# Power.net
KiCad netlist of a schematic drawn in Altium Designer
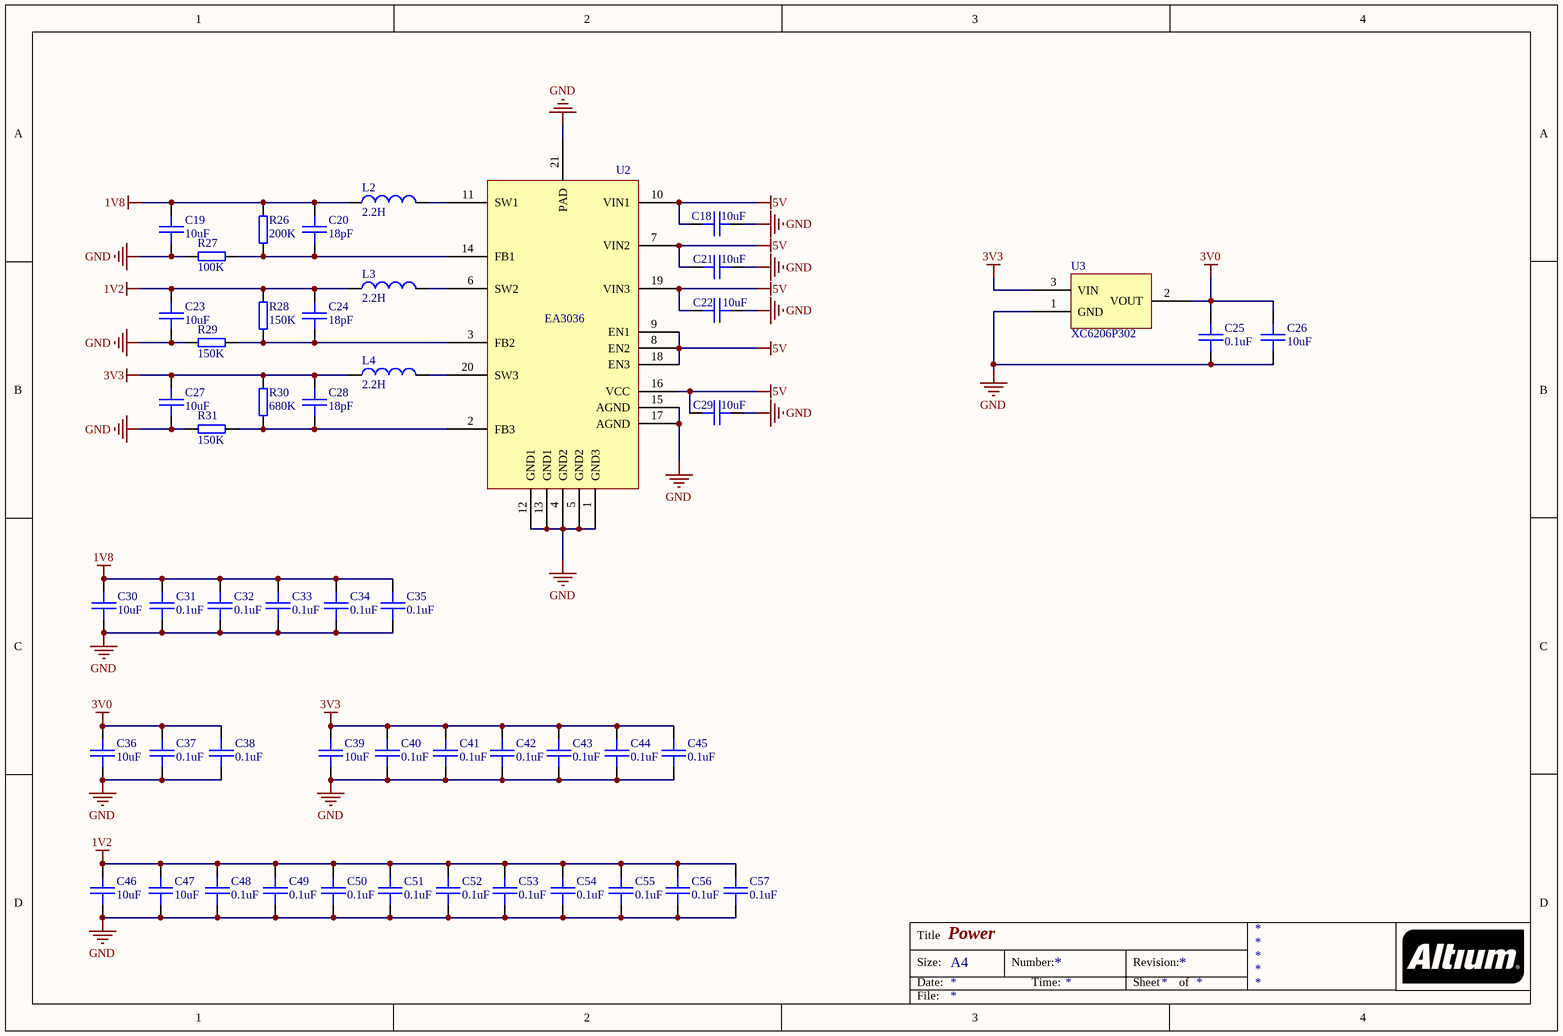
[diagram p0: Power.SchDoc]

(export (version "E")
  (design (tool "Eeschema 10.0.6"))
  (components
    (comp (ref "C18")
      (value "10uF")
      (footprint "CAP-1206")
      (description "陶瓷贴片电容1206")
      (fields (field (name "TOLERANCE") "10%") (field (name "VOLTAGE") "50V"))
      (libsource (lib "momo") (part "C_1206"))
    )
    (comp (ref "C19")
      (value "10uF")
      (footprint "CAP-1206")
      (description "陶瓷贴片电容1206")
      (fields (field (name "TOLERANCE") "10%") (field (name "VOLTAGE") "50V"))
      (libsource (lib "momo") (part "C_1206"))
    )
    (comp (ref "C20")
      (value "18pF")
      (footprint "CAP-0603")
      (description "陶瓷贴片电容0603")
      (fields (field (name "TOLERANCE") "10%") (field (name "VOLTAGE") "50V"))
      (libsource (lib "momo") (part "C_0603"))
    )
    (comp (ref "C21")
      (value "10uF")
      (footprint "CAP-1206")
      (description "陶瓷贴片电容1206")
      (fields (field (name "TOLERANCE") "10%") (field (name "VOLTAGE") "50V"))
      (libsource (lib "momo") (part "C_1206"))
    )
    (comp (ref "C22")
      (value "10uF")
      (footprint "CAP-1206")
      (description "陶瓷贴片电容1206")
      (fields (field (name "TOLERANCE") "10%") (field (name "VOLTAGE") "50V"))
      (libsource (lib "momo") (part "C_1206"))
    )
    (comp (ref "C23")
      (value "10uF")
      (footprint "CAP-1206")
      (description "陶瓷贴片电容1206")
      (fields (field (name "TOLERANCE") "10%") (field (name "VOLTAGE") "50V"))
      (libsource (lib "momo") (part "C_1206"))
    )
    (comp (ref "C24")
      (value "18pF")
      (footprint "CAP-0603")
      (description "陶瓷贴片电容0603")
      (fields (field (name "TOLERANCE") "10%") (field (name "VOLTAGE") "50V"))
      (libsource (lib "momo") (part "C_0603"))
    )
    (comp (ref "C25")
      (value "0.1uF")
      (footprint "CAP-0603")
      (description "陶瓷贴片电容0603")
      (fields (field (name "TOLERANCE") "10%") (field (name "VOLTAGE") "50V"))
      (libsource (lib "momo") (part "C_0603"))
    )
    (comp (ref "C26")
      (value "10uF")
      (footprint "CAP-1206")
      (description "陶瓷贴片电容1206")
      (fields (field (name "TOLERANCE") "10%") (field (name "VOLTAGE") "50V"))
      (libsource (lib "momo") (part "C_1206"))
    )
    (comp (ref "C27")
      (value "10uF")
      (footprint "CAP-1206")
      (description "陶瓷贴片电容1206")
      (fields (field (name "TOLERANCE") "10%") (field (name "VOLTAGE") "50V"))
      (libsource (lib "momo") (part "C_1206"))
    )
    (comp (ref "C28")
      (value "18pF")
      (footprint "CAP-0603")
      (description "陶瓷贴片电容0603")
      (fields (field (name "TOLERANCE") "10%") (field (name "VOLTAGE") "50V"))
      (libsource (lib "momo") (part "C_0603"))
    )
    (comp (ref "C29")
      (value "10uF")
      (footprint "CAP-1206")
      (description "陶瓷贴片电容1206")
      (fields (field (name "TOLERANCE") "10%") (field (name "VOLTAGE") "50V"))
      (libsource (lib "momo") (part "C_1206"))
    )
    (comp (ref "C30")
      (value "10uF")
      (footprint "CAP-0603")
      (description "陶瓷贴片电容0603")
      (fields (field (name "TOLERANCE") "10%") (field (name "VOLTAGE") "50V"))
      (libsource (lib "momo") (part "C_0603"))
    )
    (comp (ref "C31")
      (value "0.1uF")
      (footprint "CAP-0603")
      (description "陶瓷贴片电容0603")
      (fields (field (name "TOLERANCE") "10%") (field (name "VOLTAGE") "50V"))
      (libsource (lib "momo") (part "C_0603"))
    )
    (comp (ref "C32")
      (value "0.1uF")
      (footprint "CAP-0603")
      (description "陶瓷贴片电容0603")
      (fields (field (name "TOLERANCE") "10%") (field (name "VOLTAGE") "50V"))
      (libsource (lib "momo") (part "C_0603"))
    )
    (comp (ref "C33")
      (value "0.1uF")
      (footprint "CAP-0603")
      (description "陶瓷贴片电容0603")
      (fields (field (name "TOLERANCE") "10%") (field (name "VOLTAGE") "50V"))
      (libsource (lib "momo") (part "C_0603"))
    )
    (comp (ref "C34")
      (value "0.1uF")
      (footprint "CAP-0603")
      (description "陶瓷贴片电容0603")
      (fields (field (name "TOLERANCE") "10%") (field (name "VOLTAGE") "50V"))
      (libsource (lib "momo") (part "C_0603"))
    )
    (comp (ref "C35")
      (value "0.1uF")
      (footprint "CAP-0603")
      (description "陶瓷贴片电容0603")
      (fields (field (name "TOLERANCE") "10%") (field (name "VOLTAGE") "50V"))
      (libsource (lib "momo") (part "C_0603"))
    )
    (comp (ref "C36")
      (value "10uF")
      (footprint "CAP-0603")
      (description "陶瓷贴片电容0603")
      (fields (field (name "TOLERANCE") "10%") (field (name "VOLTAGE") "50V"))
      (libsource (lib "momo") (part "C_0603"))
    )
    (comp (ref "C37")
      (value "0.1uF")
      (footprint "CAP-0603")
      (description "陶瓷贴片电容0603")
      (fields (field (name "TOLERANCE") "10%") (field (name "VOLTAGE") "50V"))
      (libsource (lib "momo") (part "C_0603"))
    )
    (comp (ref "C38")
      (value "0.1uF")
      (footprint "CAP-0603")
      (description "陶瓷贴片电容0603")
      (fields (field (name "TOLERANCE") "10%") (field (name "VOLTAGE") "50V"))
      (libsource (lib "momo") (part "C_0603"))
    )
    (comp (ref "C39")
      (value "10uF")
      (footprint "CAP-0603")
      (description "陶瓷贴片电容0603")
      (fields (field (name "TOLERANCE") "10%") (field (name "VOLTAGE") "50V"))
      (libsource (lib "momo") (part "C_0603"))
    )
    (comp (ref "C40")
      (value "0.1uF")
      (footprint "CAP-0603")
      (description "陶瓷贴片电容0603")
      (fields (field (name "TOLERANCE") "10%") (field (name "VOLTAGE") "50V"))
      (libsource (lib "momo") (part "C_0603"))
    )
    (comp (ref "C41")
      (value "0.1uF")
      (footprint "CAP-0603")
      (description "陶瓷贴片电容0603")
      (fields (field (name "TOLERANCE") "10%") (field (name "VOLTAGE") "50V"))
      (libsource (lib "momo") (part "C_0603"))
    )
    (comp (ref "C42")
      (value "0.1uF")
      (footprint "CAP-0603")
      (description "陶瓷贴片电容0603")
      (fields (field (name "TOLERANCE") "10%") (field (name "VOLTAGE") "50V"))
      (libsource (lib "momo") (part "C_0603"))
    )
    (comp (ref "C43")
      (value "0.1uF")
      (footprint "CAP-0603")
      (description "陶瓷贴片电容0603")
      (fields (field (name "TOLERANCE") "10%") (field (name "VOLTAGE") "50V"))
      (libsource (lib "momo") (part "C_0603"))
    )
    (comp (ref "C44")
      (value "0.1uF")
      (footprint "CAP-0603")
      (description "陶瓷贴片电容0603")
      (fields (field (name "TOLERANCE") "10%") (field (name "VOLTAGE") "50V"))
      (libsource (lib "momo") (part "C_0603"))
    )
    (comp (ref "C45")
      (value "0.1uF")
      (footprint "CAP-0603")
      (description "陶瓷贴片电容0603")
      (fields (field (name "TOLERANCE") "10%") (field (name "VOLTAGE") "50V"))
      (libsource (lib "momo") (part "C_0603"))
    )
    (comp (ref "C46")
      (value "10uF")
      (footprint "CAP-0603")
      (description "陶瓷贴片电容0603")
      (fields (field (name "TOLERANCE") "10%") (field (name "VOLTAGE") "50V"))
      (libsource (lib "momo") (part "C_0603"))
    )
    (comp (ref "C47")
      (value "10uF")
      (footprint "CAP-0603")
      (description "陶瓷贴片电容0603")
      (fields (field (name "TOLERANCE") "10%") (field (name "VOLTAGE") "50V"))
      (libsource (lib "momo") (part "C_0603"))
    )
    (comp (ref "C48")
      (value "0.1uF")
      (footprint "CAP-0603")
      (description "陶瓷贴片电容0603")
      (fields (field (name "TOLERANCE") "10%") (field (name "VOLTAGE") "50V"))
      (libsource (lib "momo") (part "C_0603"))
    )
    (comp (ref "C49")
      (value "0.1uF")
      (footprint "CAP-0603")
      (description "陶瓷贴片电容0603")
      (fields (field (name "TOLERANCE") "10%") (field (name "VOLTAGE") "50V"))
      (libsource (lib "momo") (part "C_0603"))
    )
    (comp (ref "C50")
      (value "0.1uF")
      (footprint "CAP-0603")
      (description "陶瓷贴片电容0603")
      (fields (field (name "TOLERANCE") "10%") (field (name "VOLTAGE") "50V"))
      (libsource (lib "momo") (part "C_0603"))
    )
    (comp (ref "C51")
      (value "0.1uF")
      (footprint "CAP-0603")
      (description "陶瓷贴片电容0603")
      (fields (field (name "TOLERANCE") "10%") (field (name "VOLTAGE") "50V"))
      (libsource (lib "momo") (part "C_0603"))
    )
    (comp (ref "C52")
      (value "0.1uF")
      (footprint "CAP-0603")
      (description "陶瓷贴片电容0603")
      (fields (field (name "TOLERANCE") "10%") (field (name "VOLTAGE") "50V"))
      (libsource (lib "momo") (part "C_0603"))
    )
    (comp (ref "C53")
      (value "0.1uF")
      (footprint "CAP-0603")
      (description "陶瓷贴片电容0603")
      (fields (field (name "TOLERANCE") "10%") (field (name "VOLTAGE") "50V"))
      (libsource (lib "momo") (part "C_0603"))
    )
    (comp (ref "C54")
      (value "0.1uF")
      (footprint "CAP-0603")
      (description "陶瓷贴片电容0603")
      (fields (field (name "TOLERANCE") "10%") (field (name "VOLTAGE") "50V"))
      (libsource (lib "momo") (part "C_0603"))
    )
    (comp (ref "C55")
      (value "0.1uF")
      (footprint "CAP-0603")
      (description "陶瓷贴片电容0603")
      (fields (field (name "TOLERANCE") "10%") (field (name "VOLTAGE") "50V"))
      (libsource (lib "momo") (part "C_0603"))
    )
    (comp (ref "C56")
      (value "0.1uF")
      (footprint "CAP-0603")
      (description "陶瓷贴片电容0603")
      (fields (field (name "TOLERANCE") "10%") (field (name "VOLTAGE") "50V"))
      (libsource (lib "momo") (part "C_0603"))
    )
    (comp (ref "C57")
      (value "0.1uF")
      (footprint "CAP-0603")
      (description "陶瓷贴片电容0603")
      (fields (field (name "TOLERANCE") "10%") (field (name "VOLTAGE") "50V"))
      (libsource (lib "momo") (part "C_0603"))
    )
    (comp (ref "L2")
      (value "2.2H")
      (footprint "L-PWR-6028")
      (description "功率电感")
      (fields (field (name "TOLERANCE") "20%"))
      (libsource (lib "momo") (part "L_Power"))
    )
    (comp (ref "L3")
      (value "2.2H")
      (footprint "L-PWR-6028")
      (description "功率电感")
      (fields (field (name "TOLERANCE") "20%"))
      (libsource (lib "momo") (part "L_Power"))
    )
    (comp (ref "L4")
      (value "2.2H")
      (footprint "L-PWR-6028")
      (description "功率电感")
      (fields (field (name "TOLERANCE") "20%"))
      (libsource (lib "momo") (part "L_Power"))
    )
    (comp (ref "R26")
      (value "200K")
      (footprint "RES-0603")
      (description "贴片电阻0603")
      (fields (field (name "TOLERANCE") "5%") (field (name "VOLTAGE") "50V"))
      (libsource (lib "momo") (part "R_0603"))
    )
    (comp (ref "R27")
      (value "100K")
      (footprint "RES-0603")
      (description "贴片电阻0603")
      (fields (field (name "TOLERANCE") "5%") (field (name "VOLTAGE") "50V"))
      (libsource (lib "momo") (part "R_0603"))
    )
    (comp (ref "R28")
      (value "150K")
      (footprint "RES-0603")
      (description "贴片电阻0603")
      (fields (field (name "TOLERANCE") "5%") (field (name "VOLTAGE") "50V"))
      (libsource (lib "momo") (part "R_0603"))
    )
    (comp (ref "R29")
      (value "150K")
      (footprint "RES-0603")
      (description "贴片电阻0603")
      (fields (field (name "TOLERANCE") "5%") (field (name "VOLTAGE") "50V"))
      (libsource (lib "momo") (part "R_0603"))
    )
    (comp (ref "R30")
      (value "680K")
      (footprint "RES-0603")
      (description "贴片电阻0603")
      (fields (field (name "TOLERANCE") "5%") (field (name "VOLTAGE") "50V"))
      (libsource (lib "momo") (part "R_0603"))
    )
    (comp (ref "R31")
      (value "150K")
      (footprint "RES-0603")
      (description "贴片电阻0603")
      (fields (field (name "TOLERANCE") "5%") (field (name "VOLTAGE") "50V"))
      (libsource (lib "momo") (part "R_0603"))
    )
    (comp (ref "U2")
      (value "EA3036")
      (footprint "QFN20-3X3")
      (description "3CH Power Management IC")
      (libsource (lib "momo") (part "EA3036"))
    )
    (comp (ref "U3")
      (value "XC6206P302")
      (footprint "SOT-23-3L")
      (description "XC6206 LDO=3V")
      (libsource (lib "momo") (part "XC6206"))
    )
  )
  (nets
    (net (code "1") (name "1V2") (class "Default")
      (node (ref "C23") (pin "2") (pinfunction "2_2") (pintype "passive"))
      (node (ref "C24") (pin "1") (pinfunction "1_1") (pintype "passive"))
      (node (ref "C46") (pin "1") (pinfunction "1_1") (pintype "passive"))
      (node (ref "C47") (pin "1") (pinfunction "1_1") (pintype "passive"))
      (node (ref "C48") (pin "1") (pinfunction "1_1") (pintype "passive"))
      (node (ref "C49") (pin "1") (pinfunction "1_1") (pintype "passive"))
      (node (ref "C50") (pin "1") (pinfunction "1_1") (pintype "passive"))
      (node (ref "C51") (pin "1") (pinfunction "1_1") (pintype "passive"))
      (node (ref "C52") (pin "1") (pinfunction "1_1") (pintype "passive"))
      (node (ref "C53") (pin "1") (pinfunction "1_1") (pintype "passive"))
      (node (ref "C54") (pin "1") (pinfunction "1_1") (pintype "passive"))
      (node (ref "C55") (pin "1") (pinfunction "1_1") (pintype "passive"))
      (node (ref "C56") (pin "1") (pinfunction "1_1") (pintype "passive"))
      (node (ref "C57") (pin "1") (pinfunction "1_1") (pintype "passive"))
      (node (ref "L3") (pin "1") (pinfunction "1_1") (pintype "passive"))
      (node (ref "R28") (pin "2") (pinfunction "2_2") (pintype "passive"))
    )
    (net (code "2") (name "1V8") (class "Default")
      (node (ref "C19") (pin "2") (pinfunction "2_2") (pintype "passive"))
      (node (ref "C20") (pin "1") (pinfunction "1_1") (pintype "passive"))
      (node (ref "C30") (pin "1") (pinfunction "1_1") (pintype "passive"))
      (node (ref "C31") (pin "1") (pinfunction "1_1") (pintype "passive"))
      (node (ref "C32") (pin "1") (pinfunction "1_1") (pintype "passive"))
      (node (ref "C33") (pin "1") (pinfunction "1_1") (pintype "passive"))
      (node (ref "C34") (pin "1") (pinfunction "1_1") (pintype "passive"))
      (node (ref "C35") (pin "1") (pinfunction "1_1") (pintype "passive"))
      (node (ref "L2") (pin "1") (pinfunction "1_1") (pintype "passive"))
      (node (ref "R26") (pin "2") (pinfunction "2_2") (pintype "passive"))
    )
    (net (code "3") (name "3V0") (class "Default")
      (node (ref "C25") (pin "1") (pinfunction "1_1") (pintype "passive"))
      (node (ref "C26") (pin "1") (pinfunction "1_1") (pintype "passive"))
      (node (ref "C36") (pin "1") (pinfunction "1_1") (pintype "passive"))
      (node (ref "C37") (pin "1") (pinfunction "1_1") (pintype "passive"))
      (node (ref "C38") (pin "1") (pinfunction "1_1") (pintype "passive"))
      (node (ref "U3") (pin "2") (pinfunction "VOUT_2") (pintype "power_in"))
    )
    (net (code "4") (name "3V3") (class "Default")
      (node (ref "C27") (pin "2") (pinfunction "2_2") (pintype "passive"))
      (node (ref "C28") (pin "1") (pinfunction "1_1") (pintype "passive"))
      (node (ref "C39") (pin "1") (pinfunction "1_1") (pintype "passive"))
      (node (ref "C40") (pin "1") (pinfunction "1_1") (pintype "passive"))
      (node (ref "C41") (pin "1") (pinfunction "1_1") (pintype "passive"))
      (node (ref "C42") (pin "1") (pinfunction "1_1") (pintype "passive"))
      (node (ref "C43") (pin "1") (pinfunction "1_1") (pintype "passive"))
      (node (ref "C44") (pin "1") (pinfunction "1_1") (pintype "passive"))
      (node (ref "C45") (pin "1") (pinfunction "1_1") (pintype "passive"))
      (node (ref "L4") (pin "1") (pinfunction "1_1") (pintype "passive"))
      (node (ref "R30") (pin "2") (pinfunction "2_2") (pintype "passive"))
      (node (ref "U3") (pin "3") (pinfunction "VIN_3") (pintype "power_in"))
    )
    (net (code "5") (name "5V") (class "Default")
      (node (ref "C18") (pin "2") (pinfunction "2_2") (pintype "passive"))
      (node (ref "C21") (pin "2") (pinfunction "2_2") (pintype "passive"))
      (node (ref "C22") (pin "2") (pinfunction "2_2") (pintype "passive"))
      (node (ref "C29") (pin "2") (pinfunction "2_2") (pintype "passive"))
      (node (ref "U2") (pin "10") (pinfunction "VIN1_10") (pintype "power_in"))
      (node (ref "U2") (pin "16") (pinfunction "VCC_16") (pintype "power_in"))
      (node (ref "U2") (pin "18") (pinfunction "EN3_18") (pintype "power_in"))
      (node (ref "U2") (pin "19") (pinfunction "VIN3_19") (pintype "power_in"))
      (node (ref "U2") (pin "7") (pinfunction "VIN2_7") (pintype "power_in"))
      (node (ref "U2") (pin "8") (pinfunction "EN2_8") (pintype "power_in"))
      (node (ref "U2") (pin "9") (pinfunction "EN1_9") (pintype "power_in"))
    )
    (net (code "6") (name "GND") (class "Default")
      (node (ref "C18") (pin "1") (pinfunction "1_1") (pintype "passive"))
      (node (ref "C19") (pin "1") (pinfunction "1_1") (pintype "passive"))
      (node (ref "C21") (pin "1") (pinfunction "1_1") (pintype "passive"))
      (node (ref "C22") (pin "1") (pinfunction "1_1") (pintype "passive"))
      (node (ref "C23") (pin "1") (pinfunction "1_1") (pintype "passive"))
      (node (ref "C25") (pin "2") (pinfunction "2_2") (pintype "passive"))
      (node (ref "C26") (pin "2") (pinfunction "2_2") (pintype "passive"))
      (node (ref "C27") (pin "1") (pinfunction "1_1") (pintype "passive"))
      (node (ref "C29") (pin "1") (pinfunction "1_1") (pintype "passive"))
      (node (ref "C30") (pin "2") (pinfunction "2_2") (pintype "passive"))
      (node (ref "C31") (pin "2") (pinfunction "2_2") (pintype "passive"))
      (node (ref "C32") (pin "2") (pinfunction "2_2") (pintype "passive"))
      (node (ref "C33") (pin "2") (pinfunction "2_2") (pintype "passive"))
      (node (ref "C34") (pin "2") (pinfunction "2_2") (pintype "passive"))
      (node (ref "C35") (pin "2") (pinfunction "2_2") (pintype "passive"))
      (node (ref "C36") (pin "2") (pinfunction "2_2") (pintype "passive"))
      (node (ref "C37") (pin "2") (pinfunction "2_2") (pintype "passive"))
      (node (ref "C38") (pin "2") (pinfunction "2_2") (pintype "passive"))
      (node (ref "C39") (pin "2") (pinfunction "2_2") (pintype "passive"))
      (node (ref "C40") (pin "2") (pinfunction "2_2") (pintype "passive"))
      (node (ref "C41") (pin "2") (pinfunction "2_2") (pintype "passive"))
      (node (ref "C42") (pin "2") (pinfunction "2_2") (pintype "passive"))
      (node (ref "C43") (pin "2") (pinfunction "2_2") (pintype "passive"))
      (node (ref "C44") (pin "2") (pinfunction "2_2") (pintype "passive"))
      (node (ref "C45") (pin "2") (pinfunction "2_2") (pintype "passive"))
      (node (ref "C46") (pin "2") (pinfunction "2_2") (pintype "passive"))
      (node (ref "C47") (pin "2") (pinfunction "2_2") (pintype "passive"))
      (node (ref "C48") (pin "2") (pinfunction "2_2") (pintype "passive"))
      (node (ref "C49") (pin "2") (pinfunction "2_2") (pintype "passive"))
      (node (ref "C50") (pin "2") (pinfunction "2_2") (pintype "passive"))
      (node (ref "C51") (pin "2") (pinfunction "2_2") (pintype "passive"))
      (node (ref "C52") (pin "2") (pinfunction "2_2") (pintype "passive"))
      (node (ref "C53") (pin "2") (pinfunction "2_2") (pintype "passive"))
      (node (ref "C54") (pin "2") (pinfunction "2_2") (pintype "passive"))
      (node (ref "C55") (pin "2") (pinfunction "2_2") (pintype "passive"))
      (node (ref "C56") (pin "2") (pinfunction "2_2") (pintype "passive"))
      (node (ref "C57") (pin "2") (pinfunction "2_2") (pintype "passive"))
      (node (ref "R27") (pin "2") (pinfunction "2_2") (pintype "passive"))
      (node (ref "R29") (pin "2") (pinfunction "2_2") (pintype "passive"))
      (node (ref "R31") (pin "2") (pinfunction "2_2") (pintype "passive"))
      (node (ref "U2") (pin "1") (pinfunction "GND3_1") (pintype "power_in"))
      (node (ref "U2") (pin "12") (pinfunction "GND1_12") (pintype "power_in"))
      (node (ref "U2") (pin "13") (pinfunction "GND1_13") (pintype "power_in"))
      (node (ref "U2") (pin "15") (pinfunction "AGND_15") (pintype "power_in"))
      (node (ref "U2") (pin "17") (pinfunction "AGND_17") (pintype "power_in"))
      (node (ref "U2") (pin "21") (pinfunction "PAD_21") (pintype "power_in"))
      (node (ref "U2") (pin "4") (pinfunction "GND2_4") (pintype "power_in"))
      (node (ref "U2") (pin "5") (pinfunction "GND2_5") (pintype "power_in"))
      (node (ref "U3") (pin "1") (pinfunction "GND_1") (pintype "power_in"))
    )
    (net (code "7") (name "Net-(U2-FB1)") (class "Default")
      (node (ref "C20") (pin "2") (pinfunction "2_2") (pintype "passive"))
      (node (ref "R26") (pin "1") (pinfunction "1_1") (pintype "passive"))
      (node (ref "R27") (pin "1") (pinfunction "1_1") (pintype "passive"))
      (node (ref "U2") (pin "14") (pinfunction "FB1_14") (pintype "passive"))
    )
    (net (code "8") (name "Net-(U2-FB2)") (class "Default")
      (node (ref "C24") (pin "2") (pinfunction "2_2") (pintype "passive"))
      (node (ref "R28") (pin "1") (pinfunction "1_1") (pintype "passive"))
      (node (ref "R29") (pin "1") (pinfunction "1_1") (pintype "passive"))
      (node (ref "U2") (pin "3") (pinfunction "FB2_3") (pintype "passive"))
    )
    (net (code "9") (name "Net-(U2-FB3)") (class "Default")
      (node (ref "C28") (pin "2") (pinfunction "2_2") (pintype "passive"))
      (node (ref "R30") (pin "1") (pinfunction "1_1") (pintype "passive"))
      (node (ref "R31") (pin "1") (pinfunction "1_1") (pintype "passive"))
      (node (ref "U2") (pin "2") (pinfunction "FB3_2") (pintype "passive"))
    )
    (net (code "10") (name "Net-(U2-SW1)") (class "Default")
      (node (ref "L2") (pin "2") (pinfunction "2_2") (pintype "passive"))
      (node (ref "U2") (pin "11") (pinfunction "SW1_11") (pintype "passive"))
    )
    (net (code "11") (name "Net-(U2-SW2)") (class "Default")
      (node (ref "L3") (pin "2") (pinfunction "2_2") (pintype "passive"))
      (node (ref "U2") (pin "6") (pinfunction "SW2_6") (pintype "passive"))
    )
    (net (code "12") (name "Net-(U2-SW3)") (class "Default")
      (node (ref "L4") (pin "2") (pinfunction "2_2") (pintype "passive"))
      (node (ref "U2") (pin "20") (pinfunction "SW3_20") (pintype "passive"))
    )
  )
)
